# LightingUPS-Sensor_v1-1.net
KiCad netlist of a schematic drawn in EAGLE
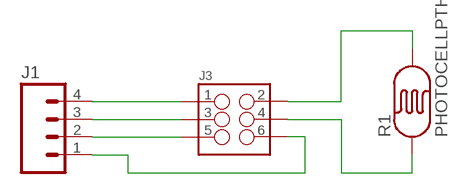
[diagram p0: schematic, sheet 1]

(export (version "E")
  (design (tool "Eeschema 10.0.6"))
  (components
    (comp (ref "J1")
      (value "M04PTH")
      (footprint "eagle-import:1X04")
      (libsource (lib "eagle-import") (part "M04PTH"))
    )
    (comp (ref "J3")
      (value "M03X2SHROUD")
      (footprint "eagle-import:2X3-SHROUDED")
      (libsource (lib "eagle-import") (part "M03X2SHROUD"))
    )
    (comp (ref "R1")
      (value "PHOTOCELLPTH")
      (footprint "eagle-import:PHOTOCELL")
      (libsource (lib "eagle-import") (part "PHOTOCELLPTH"))
    )
  )
  (nets
    (net (code "1") (name "Net-(J1-Pad1)") (class "Default")
      (node (ref "J1") (pin "1") (pinfunction "1_1") (pintype "passive"))
      (node (ref "J3") (pin "6") (pinfunction "6_6") (pintype "bidirectional"))
    )
    (net (code "2") (name "Net-(J1-Pad2)") (class "Default")
      (node (ref "J1") (pin "2") (pinfunction "2_2") (pintype "passive"))
      (node (ref "J3") (pin "5") (pinfunction "5_5") (pintype "bidirectional"))
    )
    (net (code "3") (name "Net-(J1-Pad3)") (class "Default")
      (node (ref "J1") (pin "3") (pinfunction "3_3") (pintype "passive"))
      (node (ref "J3") (pin "3") (pinfunction "3_3") (pintype "bidirectional"))
    )
    (net (code "4") (name "Net-(J1-Pad4)") (class "Default")
      (node (ref "J1") (pin "4") (pinfunction "4_4") (pintype "passive"))
      (node (ref "J3") (pin "1") (pinfunction "1_1") (pintype "bidirectional"))
    )
    (net (code "5") (name "Net-(R1-P$1)") (class "Default")
      (node (ref "J3") (pin "4") (pinfunction "4_4") (pintype "bidirectional"))
      (node (ref "R1") (pin "1") (pinfunction "P$1_1") (pintype "bidirectional"))
    )
    (net (code "6") (name "Net-(R1-P$2)") (class "Default")
      (node (ref "J3") (pin "2") (pinfunction "2_2") (pintype "bidirectional"))
      (node (ref "R1") (pin "2") (pinfunction "P$2_2") (pintype "bidirectional"))
    )
  )
)
